# Capx3_small_bypass.net
KiCad netlist of a schematic drawn in Altium Designer
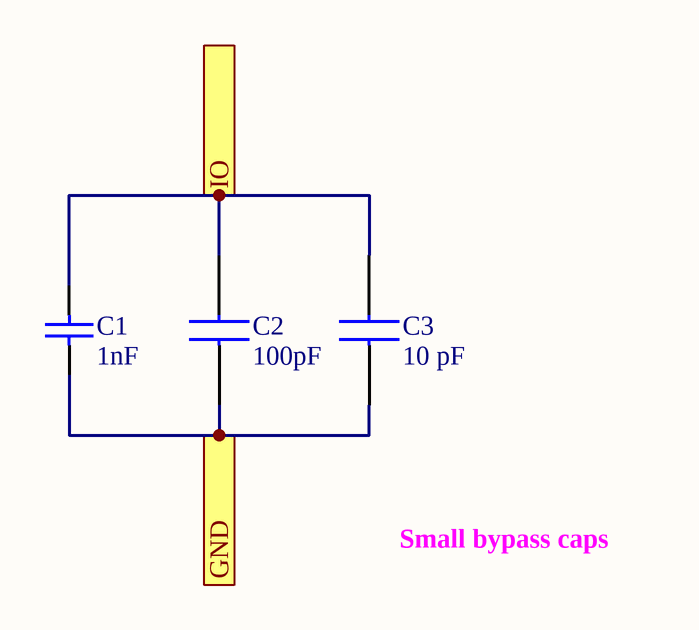
[diagram p0: Capx3_small_bypass.SchDoc]

(export (version "E")
  (design (tool "Eeschema 10.0.6"))
  (components
    (comp (ref "C1")
      (value "1nF")
      (footprint "Samsung CL21B Series")
      (fields (field (name "Comment") "Cap 1nF 0805"))
      (libsource (lib "MRI_ADC") (part "Cap 1nF 0805"))
    )
    (comp (ref "C2")
      (value "100pF")
      (footprint "CAPC1608X90N")
      (description "Capacitor")
      (fields
        (field (name "MANUFACTURER_PART_NUMBER") "06035A101FAT2A")
        (field (name "MOUSER PART NUMBER") "581-06035A101F")
      )
      (libsource (lib "IFAT6") (part "Cap 100pF 0603"))
    )
    (comp (ref "C3")
      (value "10 pF")
      (footprint "CAPC2012X88N")
      (description "Capacitor")
      (fields
        (field (name "MANUFACTURER_PART_NUMBER") "C0805C100J5GACTU")
        (field (name "MOUSER PART NUMBER") "80-C0805C100J5G")
      )
      (libsource (lib "MRI_ADC") (part "Cap 10pF 0805"))
    )
  )
  (nets
    (net (code "1") (name "/GND") (class "Default")
      (node (ref "C1") (pin "2") (pinfunction "2_2") (pintype "passive"))
      (node (ref "C2") (pin "1") (pinfunction "1_1") (pintype "passive"))
      (node (ref "C3") (pin "1") (pinfunction "1_1") (pintype "passive"))
    )
    (net (code "2") (name "/IO") (class "Default")
      (node (ref "C1") (pin "1") (pinfunction "1_1") (pintype "passive"))
      (node (ref "C2") (pin "2") (pinfunction "2_2") (pintype "passive"))
      (node (ref "C3") (pin "2") (pinfunction "2_2") (pintype "passive"))
    )
  )
)
